# Qwiic_VEML7700.net
KiCad netlist of a schematic drawn in EAGLE
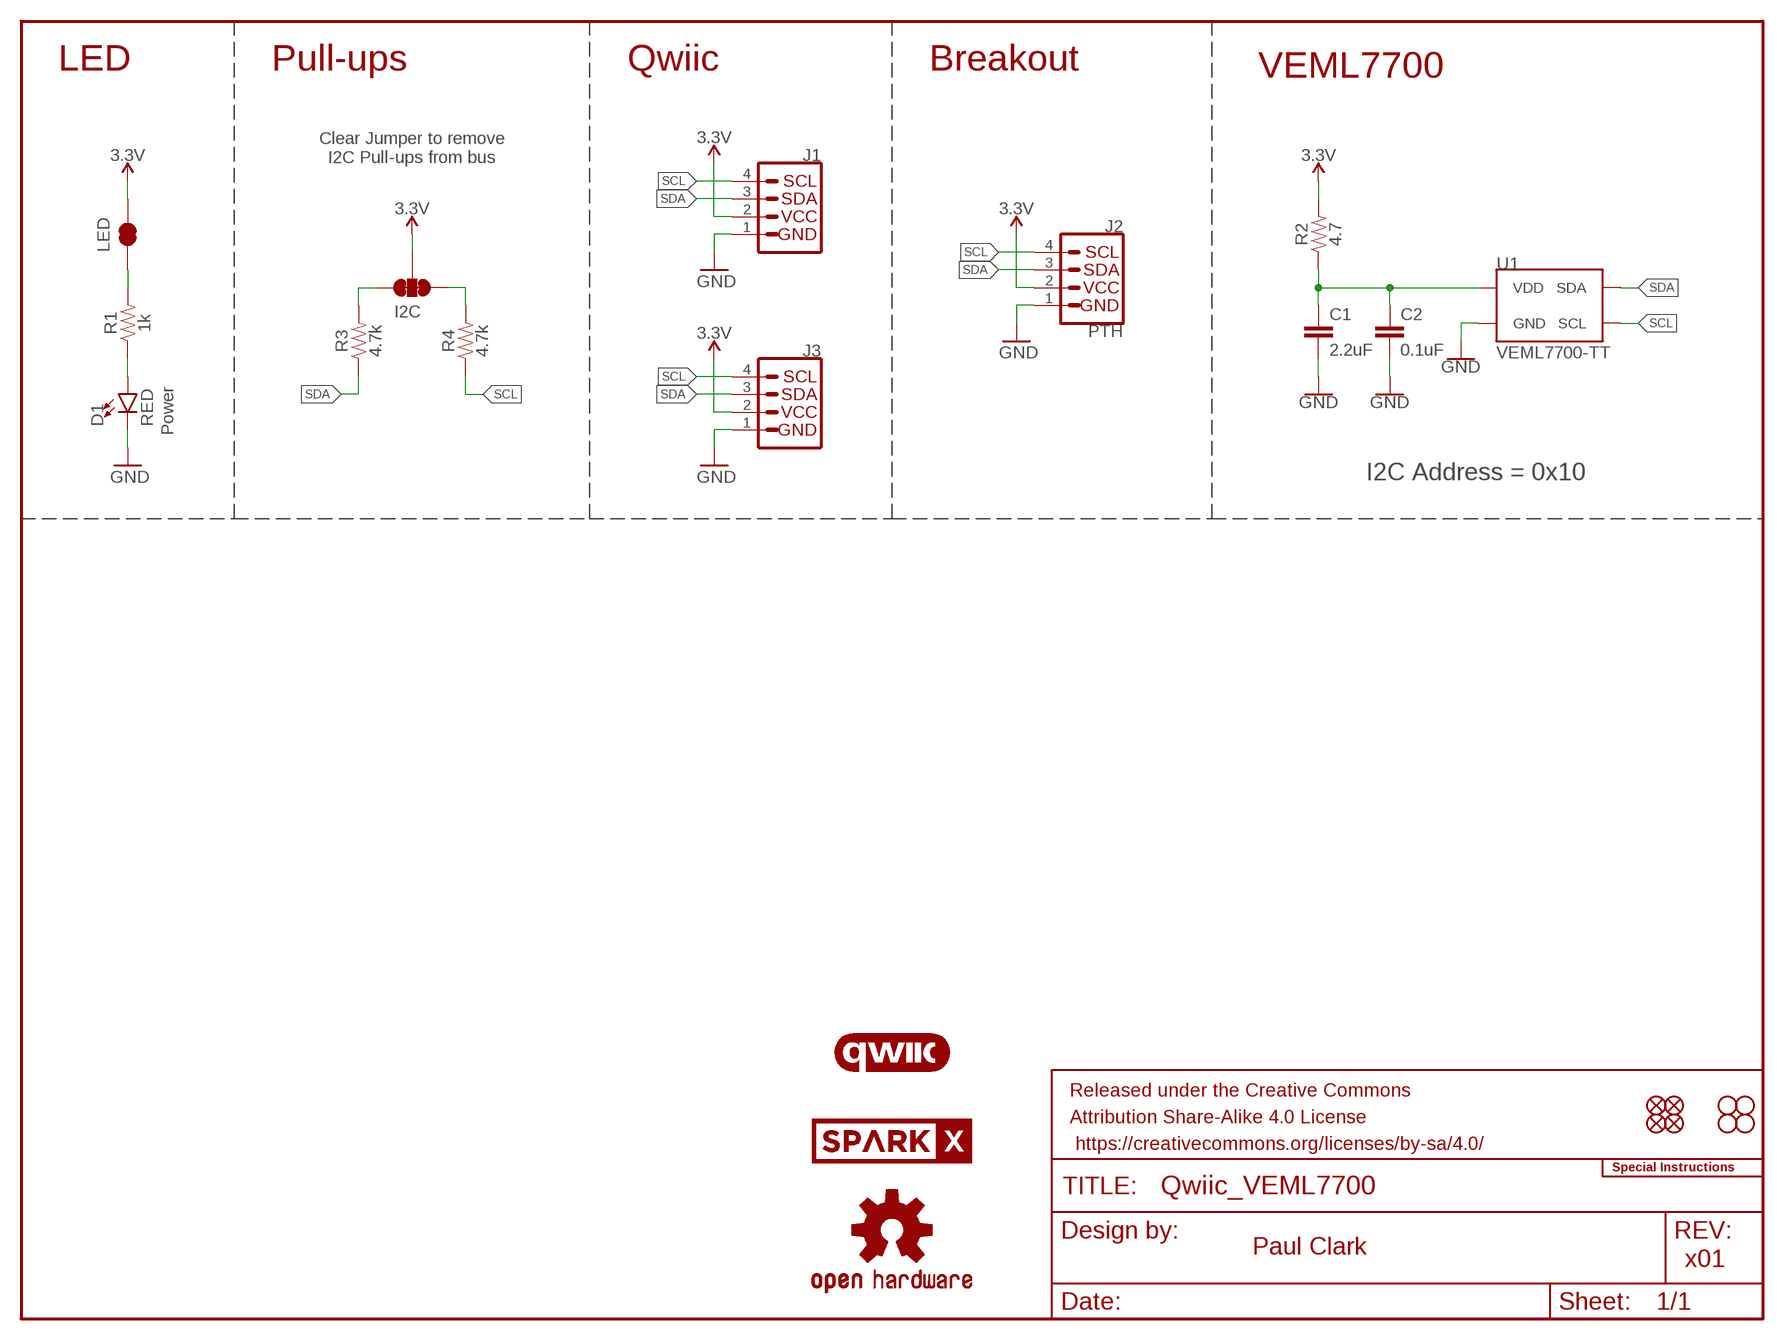
[diagram p0: schematic, sheet 1]

(export (version "E")
  (design (tool "Eeschema 10.0.6"))
  (components
    (comp (ref "C1")
      (value "2.2uF")
      (footprint "eagle-import:0402-TIGHT")
      (libsource (lib "eagle-import") (part "2.2UF-0402_TIGHT-10V-10%-X5R"))
    )
    (comp (ref "C2")
      (value "0.1uF")
      (footprint "eagle-import:0402-TIGHT")
      (libsource (lib "eagle-import") (part "0.1UF-0402T-6.3V-10%-X7R"))
    )
    (comp (ref "D1")
      (value "RED")
      (footprint "eagle-import:LED-0603")
      (libsource (lib "eagle-import") (part "LED-RED0603"))
    )
    (comp (ref "FRAME1")
      (value "FRAME-LETTER")
      (footprint "eagle-import:CREATIVE_COMMONS")
      (libsource (lib "eagle-import") (part "FRAME-LETTER"))
    )
    (comp (ref "I2C")
      (value "JUMPER-SMT_3_2-NC_TRACE_SILK")
      (footprint "eagle-import:SMT-JUMPER_3_2-NC_TRACE_SILK")
      (libsource (lib "eagle-import") (part "JUMPER-SMT_3_2-NC_TRACE_SILK"))
    )
    (comp (ref "J1")
      (value "Qwiic Right Angle")
      (footprint "eagle-import:JST04_1MM_RA")
      (libsource (lib "eagle-import") (part "I2C_STANDARDQWIIC"))
    )
    (comp (ref "J2")
      (value "PTH")
      (footprint "eagle-import:1X04_NO_SILK")
      (libsource (lib "eagle-import") (part "I2C_STANDARD_NO_SILK"))
    )
    (comp (ref "J3")
      (value "Qwiic Right Angle")
      (footprint "eagle-import:JST04_1MM_RA")
      (libsource (lib "eagle-import") (part "I2C_STANDARDQWIIC"))
    )
    (comp (ref "JP1")
      (value "FIDUCIAL1X2")
      (footprint "eagle-import:FIDUCIAL-1X2")
      (libsource (lib "eagle-import") (part "FIDUCIAL1X2"))
    )
    (comp (ref "JP2")
      (value "FIDUCIAL1X2")
      (footprint "eagle-import:FIDUCIAL-1X2")
      (libsource (lib "eagle-import") (part "FIDUCIAL1X2"))
    )
    (comp (ref "JP3")
      (value "STAND-OFF")
      (footprint "eagle-import:STAND-OFF")
      (libsource (lib "eagle-import") (part "STAND-OFF"))
    )
    (comp (ref "JP4")
      (value "STAND-OFF")
      (footprint "eagle-import:STAND-OFF")
      (libsource (lib "eagle-import") (part "STAND-OFF"))
    )
    (comp (ref "JP5")
      (value "FIDUCIAL1X2")
      (footprint "eagle-import:FIDUCIAL-1X2")
      (libsource (lib "eagle-import") (part "FIDUCIAL1X2"))
    )
    (comp (ref "JP6")
      (value "FIDUCIAL1X2")
      (footprint "eagle-import:FIDUCIAL-1X2")
      (libsource (lib "eagle-import") (part "FIDUCIAL1X2"))
    )
    (comp (ref "JP7")
      (value "STAND-OFF")
      (footprint "eagle-import:STAND-OFF")
      (libsource (lib "eagle-import") (part "STAND-OFF"))
    )
    (comp (ref "JP8")
      (value "STAND-OFF")
      (footprint "eagle-import:STAND-OFF")
      (libsource (lib "eagle-import") (part "STAND-OFF"))
    )
    (comp (ref "LED")
      (value "JUMPER-SMT_2_NC_TRACE_SILK")
      (footprint "eagle-import:SMT-JUMPER_2_NC_TRACE_SILK")
      (libsource (lib "eagle-import") (part "JUMPER-SMT_2_NC_TRACE_SILK"))
    )
    (comp (ref "LOGO1")
      (value "OSHW-LOGOMINI")
      (footprint "eagle-import:OSHW-LOGO-MINI")
      (libsource (lib "eagle-import") (part "OSHW-LOGOMINI"))
    )
    (comp (ref "LOGO2")
      (value "SPECIAL_INSTRUCTIONS-ORDERING")
      (footprint "eagle-import:ORDERING_INSTRUCTIONS")
      (libsource (lib "eagle-import") (part "SPECIAL_INSTRUCTIONS-ORDERING"))
    )
    (comp (ref "LOGO3")
      (value "QWIIC_LOGO_5MM")
      (footprint "eagle-import:QWIIC_5MM")
      (libsource (lib "eagle-import") (part "QWIIC_LOGO_5MM"))
    )
    (comp (ref "LOGO4")
      (value "OSHW-LOGOMINI")
      (footprint "eagle-import:OSHW-LOGO-MINI")
      (libsource (lib "eagle-import") (part "OSHW-LOGOMINI"))
    )
    (comp (ref "R1")
      (value "1k")
      (footprint "eagle-import:0402-TIGHT")
      (libsource (lib "eagle-import") (part "1KOHM-0402T-1/16W-1%"))
    )
    (comp (ref "R2")
      (value "4.7")
      (footprint "eagle-import:0402-TIGHT")
      (libsource (lib "eagle-import") (part "4.7OHM-0402T-1/16W-1%"))
    )
    (comp (ref "R3")
      (value "4.7k")
      (footprint "eagle-import:0402-TIGHT")
      (libsource (lib "eagle-import") (part "4.7KOHM-0402T-1/16W-1%"))
    )
    (comp (ref "R4")
      (value "4.7k")
      (footprint "eagle-import:0402-TIGHT")
      (libsource (lib "eagle-import") (part "4.7KOHM-0402T-1/16W-1%"))
    )
    (comp (ref "U$2")
      (value "SPARKX-LOGO4")
      (footprint "eagle-import:SPARKX-MEDIUM")
      (libsource (lib "eagle-import") (part "SPARKX-LOGO4"))
    )
    (comp (ref "U$21")
      (value "SPARKX-LOGO4")
      (footprint "eagle-import:SPARKX-MEDIUM")
      (libsource (lib "eagle-import") (part "SPARKX-LOGO4"))
    )
    (comp (ref "U1")
      (value "VEML7700-TT")
      (footprint "eagle-import:VEML7700_TT")
      (libsource (lib "eagle-import") (part "VEML7700-TT"))
    )
  )
  (nets
    (net (code "1") (name "3.3V") (class "Default")
      (node (ref "I2C") (pin "2") (pinfunction "2_2") (pintype "passive"))
      (node (ref "J1") (pin "2") (pinfunction "2_2") (pintype "power_in"))
      (node (ref "J2") (pin "2") (pinfunction "2_2") (pintype "power_in"))
      (node (ref "J3") (pin "2") (pinfunction "2_2") (pintype "power_in"))
      (node (ref "LED") (pin "2") (pinfunction "2_2") (pintype "passive"))
      (node (ref "R2") (pin "2") (pinfunction "2_2") (pintype "passive"))
    )
    (net (code "2") (name "GND") (class "Default")
      (node (ref "C1") (pin "2") (pinfunction "2_2") (pintype "passive"))
      (node (ref "C2") (pin "2") (pinfunction "2_2") (pintype "passive"))
      (node (ref "D1") (pin "C") (pinfunction "C_C") (pintype "passive"))
      (node (ref "J1") (pin "1") (pinfunction "1_1") (pintype "power_in"))
      (node (ref "J2") (pin "1") (pinfunction "1_1") (pintype "power_in"))
      (node (ref "J3") (pin "1") (pinfunction "1_1") (pintype "power_in"))
      (node (ref "U1") (pin "3") (pinfunction "GND_3") (pintype "power_in"))
    )
    (net (code "3") (name "Net-(D1-PadA)") (class "Default")
      (node (ref "D1") (pin "A") (pinfunction "A_A") (pintype "passive"))
      (node (ref "R1") (pin "1") (pinfunction "1_1") (pintype "passive"))
    )
    (net (code "4") (name "Net-(I2C-Pad1)") (class "Default")
      (node (ref "I2C") (pin "1") (pinfunction "1_1") (pintype "passive"))
      (node (ref "R4") (pin "2") (pinfunction "2_2") (pintype "passive"))
    )
    (net (code "5") (name "Net-(I2C-Pad3)") (class "Default")
      (node (ref "I2C") (pin "3") (pinfunction "3_3") (pintype "passive"))
      (node (ref "R3") (pin "2") (pinfunction "2_2") (pintype "passive"))
    )
    (net (code "6") (name "Net-(LED-Pad1)") (class "Default")
      (node (ref "LED") (pin "1") (pinfunction "1_1") (pintype "passive"))
      (node (ref "R1") (pin "2") (pinfunction "2_2") (pintype "passive"))
    )
    (net (code "7") (name "Net-(U1-VDD)") (class "Default")
      (node (ref "C1") (pin "1") (pinfunction "1_1") (pintype "passive"))
      (node (ref "C2") (pin "1") (pinfunction "1_1") (pintype "passive"))
      (node (ref "R2") (pin "1") (pinfunction "1_1") (pintype "passive"))
      (node (ref "U1") (pin "2") (pinfunction "VDD_2") (pintype "power_in"))
    )
    (net (code "8") (name "SCL") (class "Default")
      (node (ref "J1") (pin "4") (pinfunction "4_4") (pintype "passive"))
      (node (ref "J2") (pin "4") (pinfunction "4_4") (pintype "passive"))
      (node (ref "J3") (pin "4") (pinfunction "4_4") (pintype "passive"))
      (node (ref "R4") (pin "1") (pinfunction "1_1") (pintype "passive"))
      (node (ref "U1") (pin "1") (pinfunction "SCL_1") (pintype "bidirectional"))
    )
    (net (code "9") (name "SDA") (class "Default")
      (node (ref "J1") (pin "3") (pinfunction "3_3") (pintype "passive"))
      (node (ref "J2") (pin "3") (pinfunction "3_3") (pintype "passive"))
      (node (ref "J3") (pin "3") (pinfunction "3_3") (pintype "passive"))
      (node (ref "R3") (pin "1") (pinfunction "1_1") (pintype "passive"))
      (node (ref "U1") (pin "4") (pinfunction "SDA_4") (pintype "bidirectional"))
    )
  )
)
